# blinky-lights.net
KiCad netlist of a schematic drawn in EAGLE
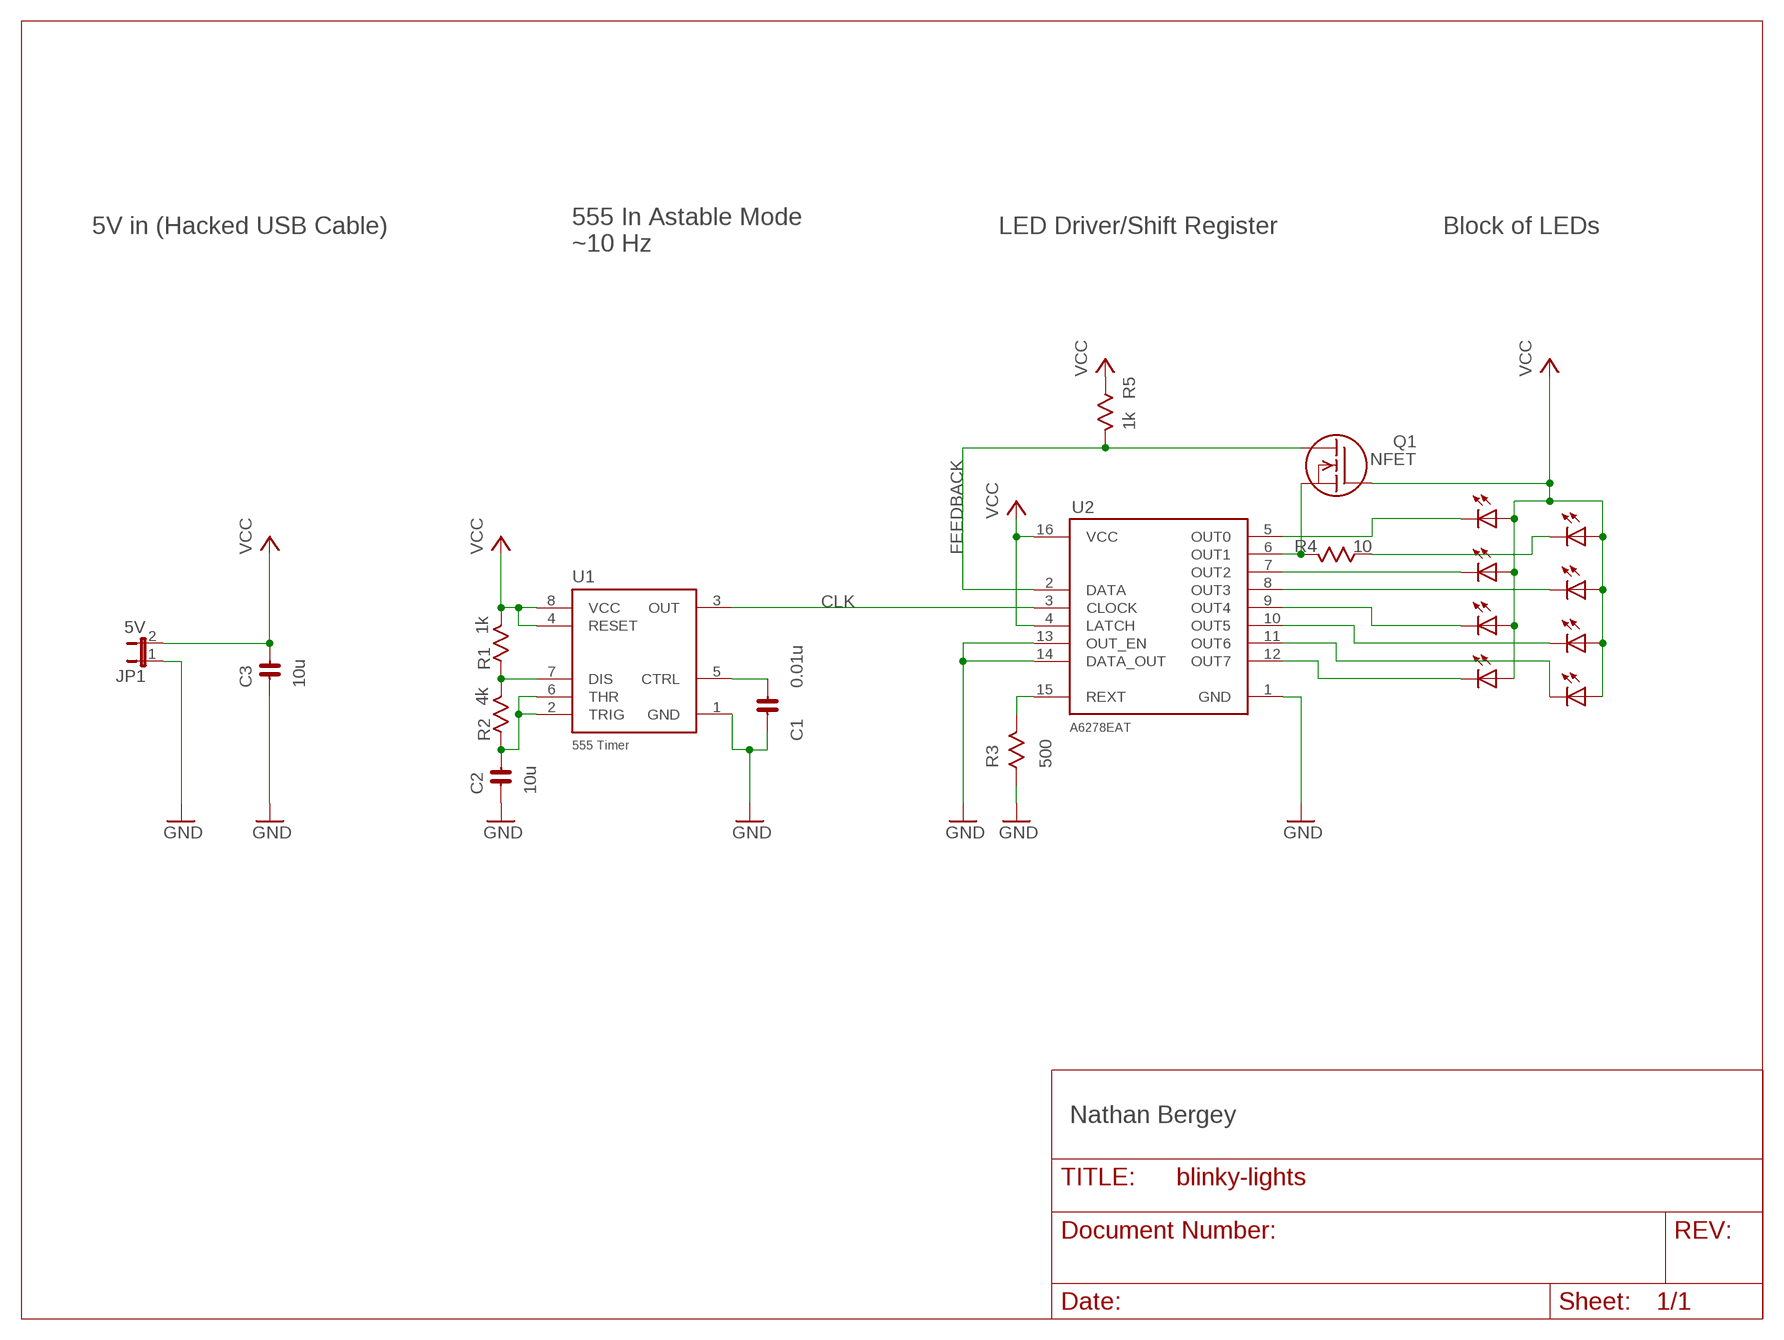
[diagram p0: schematic, sheet 1]

(export (version "E")
  (design (tool "Eeschema 10.0.6"))
  (components
    (comp (ref "C1")
      (value "0.01u")
      (footprint "eagle-import:CAP")
      (libsource (lib "eagle-import") (part "CAP"))
    )
    (comp (ref "C2")
      (value "10u")
      (footprint "eagle-import:CAP")
      (libsource (lib "eagle-import") (part "CAP"))
    )
    (comp (ref "C3")
      (value "10u")
      (footprint "eagle-import:CAP")
      (libsource (lib "eagle-import") (part "CAP"))
    )
    (comp (ref "JP1")
      (value "5V")
      (footprint "eagle-import:JP1")
      (libsource (lib "eagle-import") (part "JP1E"))
    )
    (comp (ref "LED0")
      (value "LED3MM")
      (footprint "eagle-import:LED3MM")
      (libsource (lib "eagle-import") (part "LED3MM"))
    )
    (comp (ref "LED1")
      (value "LED3MM")
      (footprint "eagle-import:LED3MM")
      (libsource (lib "eagle-import") (part "LED3MM"))
    )
    (comp (ref "LED2")
      (value "LED3MM")
      (footprint "eagle-import:LED3MM")
      (libsource (lib "eagle-import") (part "LED3MM"))
    )
    (comp (ref "LED3")
      (value "LED3MM")
      (footprint "eagle-import:LED3MM")
      (libsource (lib "eagle-import") (part "LED3MM"))
    )
    (comp (ref "LED4")
      (value "LED3MM")
      (footprint "eagle-import:LED3MM")
      (libsource (lib "eagle-import") (part "LED3MM"))
    )
    (comp (ref "LED5")
      (value "LED3MM")
      (footprint "eagle-import:LED3MM")
      (libsource (lib "eagle-import") (part "LED3MM"))
    )
    (comp (ref "LED6")
      (value "LED3MM")
      (footprint "eagle-import:LED3MM")
      (libsource (lib "eagle-import") (part "LED3MM"))
    )
    (comp (ref "LED7")
      (value "LED3MM")
      (footprint "eagle-import:LED3MM")
      (libsource (lib "eagle-import") (part "LED3MM"))
    )
    (comp (ref "Q1")
      (value "NFET")
      (footprint "eagle-import:TO92-EBC")
      (libsource (lib "eagle-import") (part "NFET"))
    )
    (comp (ref "R1")
      (value "1k")
      (footprint "eagle-import:V234_12")
      (libsource (lib "eagle-import") (part "RESISTOR"))
    )
    (comp (ref "R2")
      (value "4k")
      (footprint "eagle-import:V234_12")
      (libsource (lib "eagle-import") (part "RESISTOR"))
    )
    (comp (ref "R3")
      (value "500")
      (footprint "eagle-import:V234_12")
      (libsource (lib "eagle-import") (part "RESISTOR"))
    )
    (comp (ref "R4")
      (value "10")
      (footprint "eagle-import:V234_12")
      (libsource (lib "eagle-import") (part "RESISTOR"))
    )
    (comp (ref "R5")
      (value "1k")
      (footprint "eagle-import:V234_12")
      (libsource (lib "eagle-import") (part "RESISTOR"))
    )
    (comp (ref "U1")
      (value "555")
      (footprint "eagle-import:555")
      (libsource (lib "eagle-import") (part "555"))
    )
    (comp (ref "U2")
      (value "A2678EAT")
      (footprint "eagle-import:A6278EAT")
      (libsource (lib "eagle-import") (part "A2678EAT"))
    )
  )
  (nets
    (net (code "1") (name "/CLK") (class "Default")
      (node (ref "U1") (pin "3") (pinfunction "OUT_3") (pintype "bidirectional"))
      (node (ref "U2") (pin "3") (pinfunction "CLOCK_3") (pintype "bidirectional"))
    )
    (net (code "2") (name "/FEEDBACK") (class "Default")
      (node (ref "Q1") (pin "D") (pinfunction "D_D") (pintype "passive"))
      (node (ref "R5") (pin "2") (pinfunction "C_2") (pintype "bidirectional"))
      (node (ref "U2") (pin "2") (pinfunction "DATA_2") (pintype "bidirectional"))
    )
    (net (code "3") (name "GND") (class "Default")
      (node (ref "C1") (pin "C") (pinfunction "C_C") (pintype "bidirectional"))
      (node (ref "C2") (pin "C") (pinfunction "C_C") (pintype "bidirectional"))
      (node (ref "C3") (pin "C") (pinfunction "C_C") (pintype "bidirectional"))
      (node (ref "JP1") (pin "1") (pinfunction "1_1") (pintype "passive"))
      (node (ref "R3") (pin "1") (pinfunction "A_1") (pintype "bidirectional"))
      (node (ref "U1") (pin "1") (pinfunction "GND_1") (pintype "power_in"))
      (node (ref "U2") (pin "1") (pinfunction "GND_1") (pintype "power_in"))
      (node (ref "U2") (pin "13") (pinfunction "OUT_EN_13") (pintype "bidirectional"))
      (node (ref "U2") (pin "14") (pinfunction "DATA_OUT_14") (pintype "bidirectional"))
    )
    (net (code "4") (name "Net-(LED0-C)") (class "Default")
      (node (ref "LED0") (pin "K") (pinfunction "C_K") (pintype "passive"))
      (node (ref "U2") (pin "5") (pinfunction "OUT0_5") (pintype "bidirectional"))
    )
    (net (code "5") (name "Net-(LED1-C)") (class "Default")
      (node (ref "LED1") (pin "K") (pinfunction "C_K") (pintype "passive"))
      (node (ref "R4") (pin "1") (pinfunction "A_1") (pintype "bidirectional"))
    )
    (net (code "6") (name "Net-(LED2-C)") (class "Default")
      (node (ref "LED2") (pin "K") (pinfunction "C_K") (pintype "passive"))
      (node (ref "U2") (pin "7") (pinfunction "OUT2_7") (pintype "bidirectional"))
    )
    (net (code "7") (name "Net-(LED3-C)") (class "Default")
      (node (ref "LED3") (pin "K") (pinfunction "C_K") (pintype "passive"))
      (node (ref "U2") (pin "8") (pinfunction "OUT3_8") (pintype "bidirectional"))
    )
    (net (code "8") (name "Net-(LED4-C)") (class "Default")
      (node (ref "LED4") (pin "K") (pinfunction "C_K") (pintype "passive"))
      (node (ref "U2") (pin "9") (pinfunction "OUT4_9") (pintype "bidirectional"))
    )
    (net (code "9") (name "Net-(LED5-C)") (class "Default")
      (node (ref "LED5") (pin "K") (pinfunction "C_K") (pintype "passive"))
      (node (ref "U2") (pin "10") (pinfunction "OUT5_10") (pintype "bidirectional"))
    )
    (net (code "10") (name "Net-(LED6-C)") (class "Default")
      (node (ref "LED6") (pin "K") (pinfunction "C_K") (pintype "passive"))
      (node (ref "U2") (pin "11") (pinfunction "OUT6_11") (pintype "bidirectional"))
    )
    (net (code "11") (name "Net-(LED7-C)") (class "Default")
      (node (ref "LED7") (pin "K") (pinfunction "C_K") (pintype "passive"))
      (node (ref "U2") (pin "12") (pinfunction "OUT7_12") (pintype "bidirectional"))
    )
    (net (code "12") (name "Net-(R1-A)") (class "Default")
      (node (ref "R1") (pin "1") (pinfunction "A_1") (pintype "bidirectional"))
      (node (ref "R2") (pin "2") (pinfunction "C_2") (pintype "bidirectional"))
      (node (ref "U1") (pin "7") (pinfunction "DIS_7") (pintype "bidirectional"))
    )
    (net (code "13") (name "Net-(R2-A)") (class "Default")
      (node (ref "C2") (pin "A") (pinfunction "A_A") (pintype "bidirectional"))
      (node (ref "R2") (pin "1") (pinfunction "A_1") (pintype "bidirectional"))
      (node (ref "U1") (pin "2") (pinfunction "TRIG_2") (pintype "bidirectional"))
      (node (ref "U1") (pin "6") (pinfunction "THR_6") (pintype "bidirectional"))
    )
    (net (code "14") (name "Net-(R3-C)") (class "Default")
      (node (ref "R3") (pin "2") (pinfunction "C_2") (pintype "bidirectional"))
      (node (ref "U2") (pin "15") (pinfunction "REXT_15") (pintype "bidirectional"))
    )
    (net (code "15") (name "Net-(R4-C)") (class "Default")
      (node (ref "Q1") (pin "S") (pinfunction "S_S") (pintype "passive"))
      (node (ref "R4") (pin "2") (pinfunction "C_2") (pintype "bidirectional"))
      (node (ref "U2") (pin "6") (pinfunction "OUT1_6") (pintype "bidirectional"))
    )
    (net (code "16") (name "Net-(U1-CTRL)") (class "Default")
      (node (ref "C1") (pin "A") (pinfunction "A_A") (pintype "bidirectional"))
      (node (ref "U1") (pin "5") (pinfunction "CTRL_5") (pintype "bidirectional"))
    )
    (net (code "17") (name "VCC") (class "Default")
      (node (ref "C3") (pin "A") (pinfunction "A_A") (pintype "bidirectional"))
      (node (ref "JP1") (pin "2") (pinfunction "2_2") (pintype "passive"))
      (node (ref "LED0") (pin "A") (pinfunction "A_A") (pintype "passive"))
      (node (ref "LED1") (pin "A") (pinfunction "A_A") (pintype "passive"))
      (node (ref "LED2") (pin "A") (pinfunction "A_A") (pintype "passive"))
      (node (ref "LED3") (pin "A") (pinfunction "A_A") (pintype "passive"))
      (node (ref "LED4") (pin "A") (pinfunction "A_A") (pintype "passive"))
      (node (ref "LED5") (pin "A") (pinfunction "A_A") (pintype "passive"))
      (node (ref "LED6") (pin "A") (pinfunction "A_A") (pintype "passive"))
      (node (ref "LED7") (pin "A") (pinfunction "A_A") (pintype "passive"))
      (node (ref "Q1") (pin "G") (pinfunction "G_G") (pintype "passive"))
      (node (ref "R1") (pin "2") (pinfunction "C_2") (pintype "bidirectional"))
      (node (ref "R5") (pin "1") (pinfunction "A_1") (pintype "bidirectional"))
      (node (ref "U1") (pin "4") (pinfunction "RESET_4") (pintype "bidirectional"))
      (node (ref "U1") (pin "8") (pinfunction "VCC_8") (pintype "power_in"))
      (node (ref "U2") (pin "16") (pinfunction "VCC_16") (pintype "power_in"))
      (node (ref "U2") (pin "4") (pinfunction "LATCH_4") (pintype "bidirectional"))
    )
  )
)
